# Motor-Driver-Module_v14.net
KiCad netlist of a schematic drawn in EAGLE
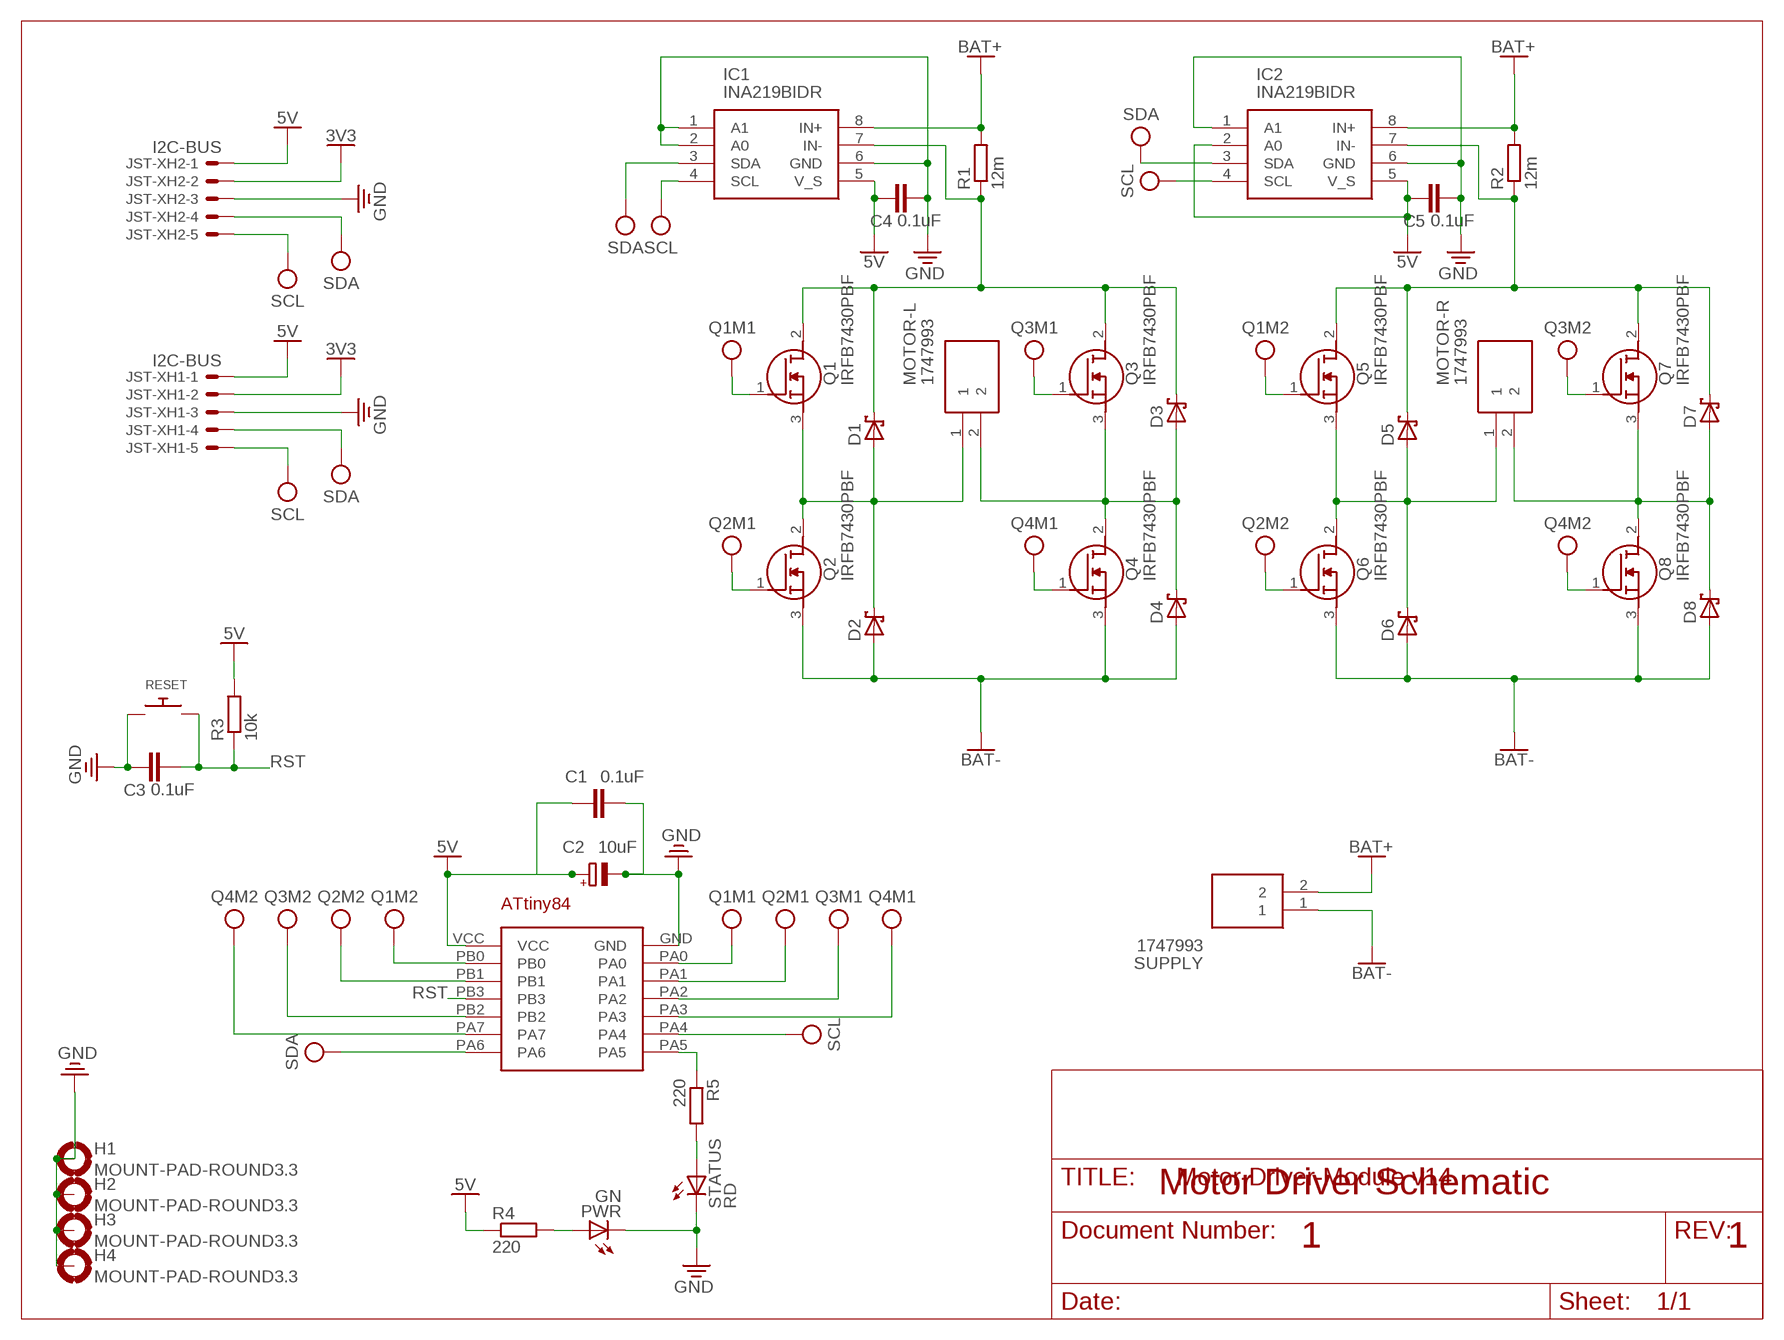
[diagram p0: schematic, sheet 1]

(export (version "E")
  (design (tool "Eeschema 10.0.6"))
  (components
    (comp (ref "C1")
      (value "0.1uF")
      (footprint "eagle-import:C025-025X050")
      (libsource (lib "eagle-import") (part "C-EU025-025X050"))
    )
    (comp (ref "C2")
      (value "10uF")
      (footprint "eagle-import:E5-10,5")
      (libsource (lib "eagle-import") (part "CPOL-EUE5-10.5"))
    )
    (comp (ref "C3")
      (value "0.1uF")
      (footprint "eagle-import:C025-030X050")
      (libsource (lib "eagle-import") (part "C-EU025-030X050"))
    )
    (comp (ref "C4")
      (value "0.1uF")
      (footprint "eagle-import:C025-030X050")
      (libsource (lib "eagle-import") (part "C-EU025-030X050"))
    )
    (comp (ref "C5")
      (value "0.1uF")
      (footprint "eagle-import:C025-030X050")
      (libsource (lib "eagle-import") (part "C-EU025-030X050"))
    )
    (comp (ref "D1")
      (value "SCHOTTKY-DIODEDO41")
      (footprint "eagle-import:DO41-10")
      (libsource (lib "eagle-import") (part "SCHOTTKY-DIODEDO41"))
    )
    (comp (ref "D2")
      (value "SCHOTTKY-DIODEDO41")
      (footprint "eagle-import:DO41-10")
      (libsource (lib "eagle-import") (part "SCHOTTKY-DIODEDO41"))
    )
    (comp (ref "D3")
      (value "SCHOTTKY-DIODEDO41")
      (footprint "eagle-import:DO41-10")
      (libsource (lib "eagle-import") (part "SCHOTTKY-DIODEDO41"))
    )
    (comp (ref "D4")
      (value "SCHOTTKY-DIODEDO41")
      (footprint "eagle-import:DO41-10")
      (libsource (lib "eagle-import") (part "SCHOTTKY-DIODEDO41"))
    )
    (comp (ref "D5")
      (value "SCHOTTKY-DIODEDO41")
      (footprint "eagle-import:DO41-10")
      (libsource (lib "eagle-import") (part "SCHOTTKY-DIODEDO41"))
    )
    (comp (ref "D6")
      (value "SCHOTTKY-DIODEDO41")
      (footprint "eagle-import:DO41-10")
      (libsource (lib "eagle-import") (part "SCHOTTKY-DIODEDO41"))
    )
    (comp (ref "D7")
      (value "SCHOTTKY-DIODEDO41")
      (footprint "eagle-import:DO41-10")
      (libsource (lib "eagle-import") (part "SCHOTTKY-DIODEDO41"))
    )
    (comp (ref "D8")
      (value "SCHOTTKY-DIODEDO41")
      (footprint "eagle-import:DO41-10")
      (libsource (lib "eagle-import") (part "SCHOTTKY-DIODEDO41"))
    )
    (comp (ref "H1")
      (value "MOUNT-PAD-ROUND3.3")
      (footprint "eagle-import:3,3-PAD")
      (libsource (lib "eagle-import") (part "MOUNT-PAD-ROUND3.3"))
    )
    (comp (ref "H2")
      (value "MOUNT-PAD-ROUND3.3")
      (footprint "eagle-import:3,3-PAD")
      (libsource (lib "eagle-import") (part "MOUNT-PAD-ROUND3.3"))
    )
    (comp (ref "H3")
      (value "MOUNT-PAD-ROUND3.3")
      (footprint "eagle-import:3,3-PAD")
      (libsource (lib "eagle-import") (part "MOUNT-PAD-ROUND3.3"))
    )
    (comp (ref "H4")
      (value "MOUNT-PAD-ROUND3.3")
      (footprint "eagle-import:3,3-PAD")
      (libsource (lib "eagle-import") (part "MOUNT-PAD-ROUND3.3"))
    )
    (comp (ref "IC1")
      (value "INA219BIDR")
      (footprint "eagle-import:SOIC127P600X175-8N")
      (fields (field (name "MOUSER_PART_NUMBER") "595-INA219BIDR"))
      (libsource (lib "eagle-import") (part "INA219BIDR"))
    )
    (comp (ref "IC2")
      (value "INA219BIDR")
      (footprint "eagle-import:SOIC127P600X175-8N")
      (fields (field (name "MOUSER_PART_NUMBER") "595-INA219BIDR"))
      (libsource (lib "eagle-import") (part "INA219BIDR"))
    )
    (comp (ref "JST-XH1")
      (value "I2C-BUS")
      (footprint "eagle-import:JST-XH-05-PACKAGE-LONG-PAD")
      (libsource (lib "eagle-import") (part "JST-XH-05-PIN-LONG-PAD"))
    )
    (comp (ref "JST-XH2")
      (value "I2C-BUS")
      (footprint "eagle-import:JST-XH-05-PACKAGE-LONG-PAD")
      (libsource (lib "eagle-import") (part "JST-XH-05-PIN-LONG-PAD"))
    )
    (comp (ref "MOTOR-L")
      (value "1747993")
      (footprint "eagle-import:1747993")
      (fields (field (name "MOUSER_PART_NUMBER") "651-1747993"))
      (libsource (lib "eagle-import") (part "1747993"))
    )
    (comp (ref "MOTOR-R")
      (value "1747993")
      (footprint "eagle-import:1747993")
      (fields (field (name "MOUSER_PART_NUMBER") "651-1747993"))
      (libsource (lib "eagle-import") (part "1747993"))
    )
    (comp (ref "PWR")
      (value "GN")
      (footprint "eagle-import:LED5MM")
      (libsource (lib "eagle-import") (part "LED5MM"))
    )
    (comp (ref "Q1")
      (value "IRFB7430PBF")
      (footprint "eagle-import:TO254P483X1016X1994-3P")
      (fields (field (name "MOUSER_PART_NUMBER") "942-IRFB7430PBF"))
      (libsource (lib "eagle-import") (part "IRFB7430PBF"))
    )
    (comp (ref "Q2")
      (value "IRFB7430PBF")
      (footprint "eagle-import:TO254P483X1016X1994-3P")
      (fields (field (name "MOUSER_PART_NUMBER") "942-IRFB7430PBF"))
      (libsource (lib "eagle-import") (part "IRFB7430PBF"))
    )
    (comp (ref "Q3")
      (value "IRFB7430PBF")
      (footprint "eagle-import:TO254P483X1016X1994-3P")
      (fields (field (name "MOUSER_PART_NUMBER") "942-IRFB7430PBF"))
      (libsource (lib "eagle-import") (part "IRFB7430PBF"))
    )
    (comp (ref "Q4")
      (value "IRFB7430PBF")
      (footprint "eagle-import:TO254P483X1016X1994-3P")
      (fields (field (name "MOUSER_PART_NUMBER") "942-IRFB7430PBF"))
      (libsource (lib "eagle-import") (part "IRFB7430PBF"))
    )
    (comp (ref "Q5")
      (value "IRFB7430PBF")
      (footprint "eagle-import:TO254P483X1016X1994-3P")
      (fields (field (name "MOUSER_PART_NUMBER") "942-IRFB7430PBF"))
      (libsource (lib "eagle-import") (part "IRFB7430PBF"))
    )
    (comp (ref "Q6")
      (value "IRFB7430PBF")
      (footprint "eagle-import:TO254P483X1016X1994-3P")
      (fields (field (name "MOUSER_PART_NUMBER") "942-IRFB7430PBF"))
      (libsource (lib "eagle-import") (part "IRFB7430PBF"))
    )
    (comp (ref "Q7")
      (value "IRFB7430PBF")
      (footprint "eagle-import:TO254P483X1016X1994-3P")
      (fields (field (name "MOUSER_PART_NUMBER") "942-IRFB7430PBF"))
      (libsource (lib "eagle-import") (part "IRFB7430PBF"))
    )
    (comp (ref "Q8")
      (value "IRFB7430PBF")
      (footprint "eagle-import:TO254P483X1016X1994-3P")
      (fields (field (name "MOUSER_PART_NUMBER") "942-IRFB7430PBF"))
      (libsource (lib "eagle-import") (part "IRFB7430PBF"))
    )
    (comp (ref "R1")
      (value "12m")
      (footprint "eagle-import:0204_7")
      (libsource (lib "eagle-import") (part "R-EU_0204/7"))
    )
    (comp (ref "R2")
      (value "12m")
      (footprint "eagle-import:0204_7")
      (libsource (lib "eagle-import") (part "R-EU_0204/7"))
    )
    (comp (ref "R3")
      (value "10k")
      (footprint "eagle-import:0204_7")
      (libsource (lib "eagle-import") (part "R-EU_0204/7"))
    )
    (comp (ref "R4")
      (value "220")
      (footprint "eagle-import:0204_7")
      (libsource (lib "eagle-import") (part "R-EU_0204/7"))
    )
    (comp (ref "R5")
      (value "220")
      (footprint "eagle-import:0204_7")
      (libsource (lib "eagle-import") (part "R-EU_0204/7"))
    )
    (comp (ref "RESET")
      (value "SWITCH_PUSHBUTTONEVQ-PE")
      (footprint "eagle-import:TACT_PANA-EVQ")
      (libsource (lib "eagle-import") (part "SWITCH_PUSHBUTTONEVQ-PE"))
    )
    (comp (ref "STATUS")
      (value "RD")
      (footprint "eagle-import:LED5MM")
      (libsource (lib "eagle-import") (part "LED5MM"))
    )
    (comp (ref "SUPPLY")
      (value "1747993")
      (footprint "eagle-import:1747993")
      (fields (field (name "MOUSER_PART_NUMBER") "651-1747993"))
      (libsource (lib "eagle-import") (part "1747993"))
    )
    (comp (ref "U$1")
      (value "ATTINY84DIP")
      (footprint "eagle-import:ATTINY84(DIP)")
      (libsource (lib "eagle-import") (part "ATTINY84DIP"))
    )
  )
  (nets
    (net (code "1") (name "/RST") (class "Default")
      (node (ref "C3") (pin "2") (pinfunction "2_2") (pintype "passive"))
      (node (ref "R3") (pin "1") (pinfunction "1_1") (pintype "passive"))
      (node (ref "RESET") (pin "P$2") (pinfunction "P$2_P$2") (pintype "passive"))
      (node (ref "U$1") (pin "PB3") (pinfunction "PB3_PB3") (pintype "bidirectional"))
    )
    (net (code "2") (name "3V3") (class "Default")
      (node (ref "JST-XH1") (pin "2") (pinfunction "S_2") (pintype "passive"))
      (node (ref "JST-XH2") (pin "2") (pinfunction "S_2") (pintype "passive"))
    )
    (net (code "3") (name "5V") (class "Default")
      (node (ref "C1") (pin "1") (pinfunction "1_1") (pintype "passive"))
      (node (ref "C2") (pin "+") (pinfunction "+_+") (pintype "passive"))
      (node (ref "C4") (pin "1") (pinfunction "1_1") (pintype "passive"))
      (node (ref "C5") (pin "1") (pinfunction "1_1") (pintype "passive"))
      (node (ref "IC1") (pin "5") (pinfunction "V_S_5") (pintype "bidirectional"))
      (node (ref "IC2") (pin "2") (pinfunction "A0_2") (pintype "bidirectional"))
      (node (ref "IC2") (pin "5") (pinfunction "V_S_5") (pintype "bidirectional"))
      (node (ref "JST-XH1") (pin "1") (pinfunction "S_1") (pintype "passive"))
      (node (ref "JST-XH2") (pin "1") (pinfunction "S_1") (pintype "passive"))
      (node (ref "R3") (pin "2") (pinfunction "2_2") (pintype "passive"))
      (node (ref "R4") (pin "1") (pinfunction "1_1") (pintype "passive"))
      (node (ref "U$1") (pin "VCC") (pinfunction "VCC_VCC") (pintype "bidirectional"))
    )
    (net (code "4") (name "BAT+") (class "Default")
      (node (ref "IC1") (pin "8") (pinfunction "IN+_8") (pintype "bidirectional"))
      (node (ref "IC2") (pin "8") (pinfunction "IN+_8") (pintype "bidirectional"))
      (node (ref "R1") (pin "2") (pinfunction "2_2") (pintype "passive"))
      (node (ref "R2") (pin "2") (pinfunction "2_2") (pintype "passive"))
      (node (ref "SUPPLY") (pin "2") (pinfunction "2_2") (pintype "bidirectional"))
    )
    (net (code "5") (name "BAT-") (class "Default")
      (node (ref "D2") (pin "A") (pinfunction "A_A") (pintype "passive"))
      (node (ref "D4") (pin "A") (pinfunction "A_A") (pintype "passive"))
      (node (ref "D6") (pin "A") (pinfunction "A_A") (pintype "passive"))
      (node (ref "D8") (pin "A") (pinfunction "A_A") (pintype "passive"))
      (node (ref "Q2") (pin "3") (pinfunction "S_3") (pintype "bidirectional"))
      (node (ref "Q4") (pin "3") (pinfunction "S_3") (pintype "bidirectional"))
      (node (ref "Q6") (pin "3") (pinfunction "S_3") (pintype "bidirectional"))
      (node (ref "Q8") (pin "3") (pinfunction "S_3") (pintype "bidirectional"))
      (node (ref "SUPPLY") (pin "1") (pinfunction "1_1") (pintype "bidirectional"))
    )
    (net (code "6") (name "GND") (class "Default")
      (node (ref "C1") (pin "2") (pinfunction "2_2") (pintype "passive"))
      (node (ref "C2") (pin "-") (pinfunction "-_-") (pintype "passive"))
      (node (ref "C3") (pin "1") (pinfunction "1_1") (pintype "passive"))
      (node (ref "C4") (pin "2") (pinfunction "2_2") (pintype "passive"))
      (node (ref "C5") (pin "2") (pinfunction "2_2") (pintype "passive"))
      (node (ref "H1") (pin "B3,3") (pinfunction "MOUNT_B3,3") (pintype "passive"))
      (node (ref "H2") (pin "B3,3") (pinfunction "MOUNT_B3,3") (pintype "passive"))
      (node (ref "H3") (pin "B3,3") (pinfunction "MOUNT_B3,3") (pintype "passive"))
      (node (ref "H4") (pin "B3,3") (pinfunction "MOUNT_B3,3") (pintype "passive"))
      (node (ref "IC1") (pin "1") (pinfunction "A1_1") (pintype "bidirectional"))
      (node (ref "IC1") (pin "2") (pinfunction "A0_2") (pintype "bidirectional"))
      (node (ref "IC1") (pin "6") (pinfunction "GND_6") (pintype "bidirectional"))
      (node (ref "IC2") (pin "1") (pinfunction "A1_1") (pintype "bidirectional"))
      (node (ref "IC2") (pin "6") (pinfunction "GND_6") (pintype "bidirectional"))
      (node (ref "JST-XH1") (pin "3") (pinfunction "S_3") (pintype "passive"))
      (node (ref "JST-XH2") (pin "3") (pinfunction "S_3") (pintype "passive"))
      (node (ref "PWR") (pin "K") (pinfunction "C_K") (pintype "passive"))
      (node (ref "RESET") (pin "P$1") (pinfunction "P$1_P$1") (pintype "passive"))
      (node (ref "STATUS") (pin "K") (pinfunction "C_K") (pintype "passive"))
      (node (ref "U$1") (pin "GND") (pinfunction "GND_GND") (pintype "bidirectional"))
    )
    (net (code "7") (name "Net-(IC1-IN-)") (class "Default")
      (node (ref "D1") (pin "C") (pinfunction "C_C") (pintype "passive"))
      (node (ref "D3") (pin "C") (pinfunction "C_C") (pintype "passive"))
      (node (ref "IC1") (pin "7") (pinfunction "IN-_7") (pintype "bidirectional"))
      (node (ref "Q1") (pin "2") (pinfunction "D_2") (pintype "bidirectional"))
      (node (ref "Q3") (pin "2") (pinfunction "D_2") (pintype "bidirectional"))
      (node (ref "R1") (pin "1") (pinfunction "1_1") (pintype "passive"))
    )
    (net (code "8") (name "Net-(IC2-IN-)") (class "Default")
      (node (ref "D5") (pin "C") (pinfunction "C_C") (pintype "passive"))
      (node (ref "D7") (pin "C") (pinfunction "C_C") (pintype "passive"))
      (node (ref "IC2") (pin "7") (pinfunction "IN-_7") (pintype "bidirectional"))
      (node (ref "Q5") (pin "2") (pinfunction "D_2") (pintype "bidirectional"))
      (node (ref "Q7") (pin "2") (pinfunction "D_2") (pintype "bidirectional"))
      (node (ref "R2") (pin "1") (pinfunction "1_1") (pintype "passive"))
    )
    (net (code "9") (name "Net-(PWR-PadA)") (class "Default")
      (node (ref "PWR") (pin "A") (pinfunction "A_A") (pintype "passive"))
      (node (ref "R4") (pin "2") (pinfunction "2_2") (pintype "passive"))
    )
    (net (code "10") (name "Net-(Q1-S)") (class "Default")
      (node (ref "D1") (pin "A") (pinfunction "A_A") (pintype "passive"))
      (node (ref "D2") (pin "C") (pinfunction "C_C") (pintype "passive"))
      (node (ref "MOTOR-L") (pin "1") (pinfunction "1_1") (pintype "bidirectional"))
      (node (ref "Q1") (pin "3") (pinfunction "S_3") (pintype "bidirectional"))
      (node (ref "Q2") (pin "2") (pinfunction "D_2") (pintype "bidirectional"))
    )
    (net (code "11") (name "Net-(Q3-S)") (class "Default")
      (node (ref "D3") (pin "A") (pinfunction "A_A") (pintype "passive"))
      (node (ref "D4") (pin "C") (pinfunction "C_C") (pintype "passive"))
      (node (ref "MOTOR-L") (pin "2") (pinfunction "2_2") (pintype "bidirectional"))
      (node (ref "Q3") (pin "3") (pinfunction "S_3") (pintype "bidirectional"))
      (node (ref "Q4") (pin "2") (pinfunction "D_2") (pintype "bidirectional"))
    )
    (net (code "12") (name "Net-(Q5-S)") (class "Default")
      (node (ref "D5") (pin "A") (pinfunction "A_A") (pintype "passive"))
      (node (ref "D6") (pin "C") (pinfunction "C_C") (pintype "passive"))
      (node (ref "MOTOR-R") (pin "1") (pinfunction "1_1") (pintype "bidirectional"))
      (node (ref "Q5") (pin "3") (pinfunction "S_3") (pintype "bidirectional"))
      (node (ref "Q6") (pin "2") (pinfunction "D_2") (pintype "bidirectional"))
    )
    (net (code "13") (name "Net-(Q7-S)") (class "Default")
      (node (ref "D7") (pin "A") (pinfunction "A_A") (pintype "passive"))
      (node (ref "D8") (pin "C") (pinfunction "C_C") (pintype "passive"))
      (node (ref "MOTOR-R") (pin "2") (pinfunction "2_2") (pintype "bidirectional"))
      (node (ref "Q7") (pin "3") (pinfunction "S_3") (pintype "bidirectional"))
      (node (ref "Q8") (pin "2") (pinfunction "D_2") (pintype "bidirectional"))
    )
    (net (code "14") (name "Net-(R5-Pad1)") (class "Default")
      (node (ref "R5") (pin "1") (pinfunction "1_1") (pintype "passive"))
      (node (ref "U$1") (pin "PA5") (pinfunction "PA5_PA5") (pintype "bidirectional"))
    )
    (net (code "15") (name "Net-(R5-Pad2)") (class "Default")
      (node (ref "R5") (pin "2") (pinfunction "2_2") (pintype "passive"))
      (node (ref "STATUS") (pin "A") (pinfunction "A_A") (pintype "passive"))
    )
    (net (code "16") (name "Q1M1") (class "Default")
      (node (ref "Q1") (pin "1") (pinfunction "G_1") (pintype "bidirectional"))
      (node (ref "U$1") (pin "PA0") (pinfunction "PA0_PA0") (pintype "bidirectional"))
    )
    (net (code "17") (name "Q1M2") (class "Default")
      (node (ref "Q5") (pin "1") (pinfunction "G_1") (pintype "bidirectional"))
      (node (ref "U$1") (pin "PB0") (pinfunction "PB0_PB0") (pintype "bidirectional"))
    )
    (net (code "18") (name "Q2M1") (class "Default")
      (node (ref "Q2") (pin "1") (pinfunction "G_1") (pintype "bidirectional"))
      (node (ref "U$1") (pin "PA1") (pinfunction "PA1_PA1") (pintype "bidirectional"))
    )
    (net (code "19") (name "Q2M2") (class "Default")
      (node (ref "Q6") (pin "1") (pinfunction "G_1") (pintype "bidirectional"))
      (node (ref "U$1") (pin "PB1") (pinfunction "PB1_PB1") (pintype "bidirectional"))
    )
    (net (code "20") (name "Q3M1") (class "Default")
      (node (ref "Q3") (pin "1") (pinfunction "G_1") (pintype "bidirectional"))
      (node (ref "U$1") (pin "PA2") (pinfunction "PA2_PA2") (pintype "bidirectional"))
    )
    (net (code "21") (name "Q3M2") (class "Default")
      (node (ref "Q7") (pin "1") (pinfunction "G_1") (pintype "bidirectional"))
      (node (ref "U$1") (pin "PB2") (pinfunction "PB2_PB2") (pintype "bidirectional"))
    )
    (net (code "22") (name "Q4M1") (class "Default")
      (node (ref "Q4") (pin "1") (pinfunction "G_1") (pintype "bidirectional"))
      (node (ref "U$1") (pin "PA3") (pinfunction "PA3_PA3") (pintype "bidirectional"))
    )
    (net (code "23") (name "Q4M2") (class "Default")
      (node (ref "Q8") (pin "1") (pinfunction "G_1") (pintype "bidirectional"))
      (node (ref "U$1") (pin "PA7") (pinfunction "PA7_PA7") (pintype "bidirectional"))
    )
    (net (code "24") (name "SCL") (class "Default")
      (node (ref "IC1") (pin "4") (pinfunction "SCL_4") (pintype "bidirectional"))
      (node (ref "IC2") (pin "4") (pinfunction "SCL_4") (pintype "bidirectional"))
      (node (ref "JST-XH1") (pin "5") (pinfunction "S_5") (pintype "passive"))
      (node (ref "JST-XH2") (pin "5") (pinfunction "S_5") (pintype "passive"))
      (node (ref "U$1") (pin "PA4") (pinfunction "PA4_PA4") (pintype "bidirectional"))
    )
    (net (code "25") (name "SDA") (class "Default")
      (node (ref "IC1") (pin "3") (pinfunction "SDA_3") (pintype "bidirectional"))
      (node (ref "IC2") (pin "3") (pinfunction "SDA_3") (pintype "bidirectional"))
      (node (ref "JST-XH1") (pin "4") (pinfunction "S_4") (pintype "passive"))
      (node (ref "JST-XH2") (pin "4") (pinfunction "S_4") (pintype "passive"))
      (node (ref "U$1") (pin "PA6") (pinfunction "PA6_PA6") (pintype "bidirectional"))
    )
  )
)
